# 8Bit-audio-7524-axelb-v2.net
KiCad netlist of a schematic drawn in EAGLE
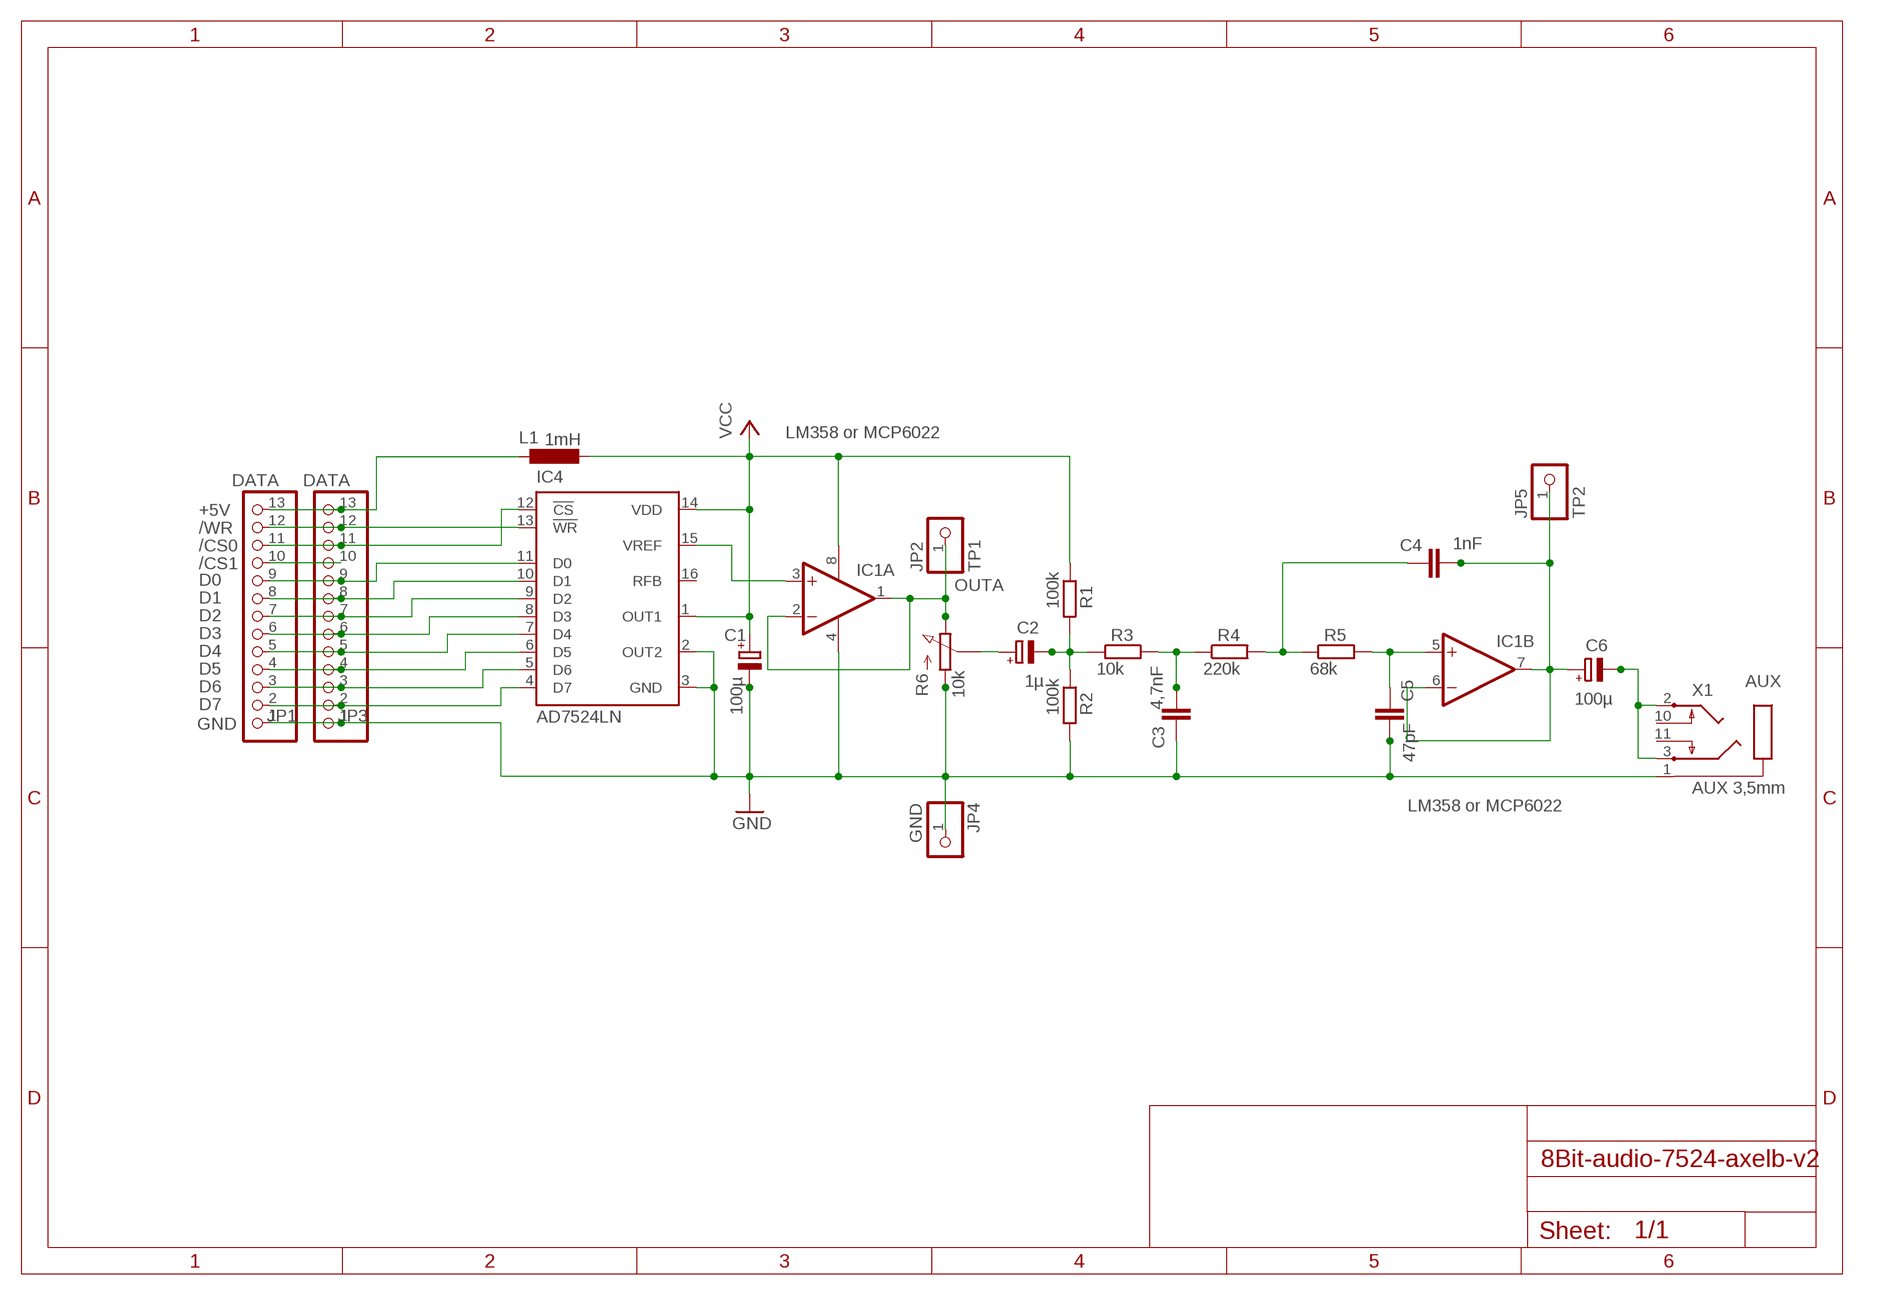
[diagram p0: schematic, sheet 1]

(export (version "E")
  (design (tool "Eeschema 10.0.6"))
  (components
    (comp (ref "C1")
      (value "100µ")
      (footprint "eagle-import:E2,5-7")
      (libsource (lib "eagle-import") (part "CPOL-EUE2.5-7"))
    )
    (comp (ref "C2")
      (value "1µ")
      (footprint "eagle-import:E2,5-7")
      (libsource (lib "eagle-import") (part "CPOL-EUE2.5-7"))
    )
    (comp (ref "C3")
      (value "4,7nF")
      (footprint "eagle-import:RCL_C025_050-055X075")
      (libsource (lib "eagle-import") (part "RCL_C-EU025_050-055X075"))
    )
    (comp (ref "C4")
      (value "1nF")
      (footprint "eagle-import:RCL_C025_050-055X075")
      (libsource (lib "eagle-import") (part "RCL_C-EU025_050-055X075"))
    )
    (comp (ref "C5")
      (value "47pF")
      (footprint "eagle-import:RCL_C025_050-055X075")
      (libsource (lib "eagle-import") (part "RCL_C-EU025_050-055X075"))
    )
    (comp (ref "C6")
      (value "100µ")
      (footprint "eagle-import:E2,5-7")
      (libsource (lib "eagle-import") (part "CPOL-EUE2.5-7"))
    )
    (comp (ref "IC1")
      (value "LM358 or MCP6022")
      (footprint "eagle-import:DIL08")
      (libsource (lib "eagle-import") (part "LM358N"))
    )
    (comp (ref "IC4")
      (value "AD7524LN")
      (footprint "eagle-import:DIL16")
      (fields (field (name "MF") "ALTERA CORPORATION") (field (name "MPN") "AD7524LNZ"))
      (libsource (lib "eagle-import") (part "AD7524NL"))
    )
    (comp (ref "JP1")
      (value "DATA")
      (footprint "eagle-import:1X13")
      (libsource (lib "eagle-import") (part "PINHD-1X13"))
    )
    (comp (ref "JP2")
      (value "TP1")
      (footprint "eagle-import:1X01")
      (libsource (lib "eagle-import") (part "PINHD-1X1"))
    )
    (comp (ref "JP3")
      (value "DATA")
      (footprint "eagle-import:1X13")
      (libsource (lib "eagle-import") (part "PINHD-1X13"))
    )
    (comp (ref "JP4")
      (value "GND")
      (footprint "eagle-import:1X01")
      (libsource (lib "eagle-import") (part "PINHD-1X1"))
    )
    (comp (ref "JP5")
      (value "TP2")
      (footprint "eagle-import:1X01")
      (libsource (lib "eagle-import") (part "PINHD-1X1"))
    )
    (comp (ref "L1")
      (value "1mH")
      (footprint "eagle-import:0207_10")
      (libsource (lib "eagle-import") (part "L-EU0207/10"))
    )
    (comp (ref "R1")
      (value "100k")
      (footprint "eagle-import:0207_10")
      (libsource (lib "eagle-import") (part "R-EU_0207/10"))
    )
    (comp (ref "R2")
      (value "100k")
      (footprint "eagle-import:0207_10")
      (libsource (lib "eagle-import") (part "R-EU_0207/10"))
    )
    (comp (ref "R3")
      (value "10k")
      (footprint "eagle-import:0207_10")
      (libsource (lib "eagle-import") (part "R-EU_0207/10"))
    )
    (comp (ref "R4")
      (value "220k")
      (footprint "eagle-import:0207_10")
      (libsource (lib "eagle-import") (part "R-EU_0207/10"))
    )
    (comp (ref "R5")
      (value "68k")
      (footprint "eagle-import:0207_10")
      (libsource (lib "eagle-import") (part "R-EU_0207/10"))
    )
    (comp (ref "R6")
      (value "10k")
      (footprint "eagle-import:POT_3RP_1610N")
      (libsource (lib "eagle-import") (part "POT_3RP/1610N"))
    )
    (comp (ref "X1")
      (value "AUX 3,5mm")
      (footprint "eagle-import:SJ1-352XN")
      (libsource (lib "eagle-import") (part "CON-SJ1-352XNSJ1-352XN"))
    )
  )
  (nets
    (net (code "1") (name "/+5V") (class "Default")
      (node (ref "JP1") (pin "13") (pinfunction "13_13") (pintype "passive"))
      (node (ref "JP3") (pin "13") (pinfunction "13_13") (pintype "passive"))
      (node (ref "L1") (pin "1") (pinfunction "1_1") (pintype "passive"))
    )
    (net (code "2") (name "/AUX") (class "Default")
      (node (ref "C6") (pin "-") (pinfunction "-_-") (pintype "passive"))
      (node (ref "C6") (pin "-1") (pinfunction "-2_-1") (pintype "passive"))
      (node (ref "X1") (pin "2") (pinfunction "2_2") (pintype "passive"))
      (node (ref "X1") (pin "3") (pinfunction "3_3") (pintype "passive"))
    )
    (net (code "3") (name "/D0") (class "Default")
      (node (ref "IC4") (pin "11") (pinfunction "D0_11") (pintype "input"))
      (node (ref "JP1") (pin "9") (pinfunction "9_9") (pintype "passive"))
      (node (ref "JP3") (pin "9") (pinfunction "9_9") (pintype "passive"))
    )
    (net (code "4") (name "/D1") (class "Default")
      (node (ref "IC4") (pin "10") (pinfunction "D1_10") (pintype "input"))
      (node (ref "JP1") (pin "8") (pinfunction "8_8") (pintype "passive"))
      (node (ref "JP3") (pin "8") (pinfunction "8_8") (pintype "passive"))
    )
    (net (code "5") (name "/D2") (class "Default")
      (node (ref "IC4") (pin "9") (pinfunction "D2_9") (pintype "input"))
      (node (ref "JP1") (pin "7") (pinfunction "7_7") (pintype "passive"))
      (node (ref "JP3") (pin "7") (pinfunction "7_7") (pintype "passive"))
    )
    (net (code "6") (name "/D3") (class "Default")
      (node (ref "IC4") (pin "8") (pinfunction "D3_8") (pintype "input"))
      (node (ref "JP1") (pin "6") (pinfunction "6_6") (pintype "passive"))
      (node (ref "JP3") (pin "6") (pinfunction "6_6") (pintype "passive"))
    )
    (net (code "7") (name "/D4") (class "Default")
      (node (ref "IC4") (pin "7") (pinfunction "D4_7") (pintype "input"))
      (node (ref "JP1") (pin "5") (pinfunction "5_5") (pintype "passive"))
      (node (ref "JP3") (pin "5") (pinfunction "5_5") (pintype "passive"))
    )
    (net (code "8") (name "/D5") (class "Default")
      (node (ref "IC4") (pin "6") (pinfunction "D5_6") (pintype "input"))
      (node (ref "JP1") (pin "4") (pinfunction "4_4") (pintype "passive"))
      (node (ref "JP3") (pin "4") (pinfunction "4_4") (pintype "passive"))
    )
    (net (code "9") (name "/D6") (class "Default")
      (node (ref "IC4") (pin "5") (pinfunction "D6_5") (pintype "input"))
      (node (ref "JP1") (pin "3") (pinfunction "3_3") (pintype "passive"))
      (node (ref "JP3") (pin "3") (pinfunction "3_3") (pintype "passive"))
    )
    (net (code "10") (name "/D7") (class "Default")
      (node (ref "IC4") (pin "4") (pinfunction "D7_4") (pintype "input"))
      (node (ref "JP1") (pin "2") (pinfunction "2_2") (pintype "passive"))
      (node (ref "JP3") (pin "2") (pinfunction "2_2") (pintype "passive"))
    )
    (net (code "11") (name "/OUTA") (class "Default")
      (node (ref "IC1") (pin "1") (pinfunction "OUT_1") (pintype "output"))
      (node (ref "IC1") (pin "2") (pinfunction "-IN_2") (pintype "input"))
      (node (ref "JP2") (pin "1") (pinfunction "1_1") (pintype "passive"))
      (node (ref "R6") (pin "E1") (pinfunction "E1_E1") (pintype "passive"))
      (node (ref "R6") (pin "E2") (pinfunction "E2_E2") (pintype "passive"))
    )
    (net (code "12") (name "/{slash}CS0") (class "Default")
      (node (ref "IC4") (pin "12") (pinfunction "~{CS}_12") (pintype "input"))
      (node (ref "JP1") (pin "11") (pinfunction "11_11") (pintype "passive"))
      (node (ref "JP3") (pin "11") (pinfunction "11_11") (pintype "passive"))
    )
    (net (code "13") (name "/{slash}CS1") (class "Default")
      (node (ref "JP1") (pin "10") (pinfunction "10_10") (pintype "passive"))
      (node (ref "JP3") (pin "10") (pinfunction "10_10") (pintype "passive"))
    )
    (net (code "14") (name "/{slash}WR") (class "Default")
      (node (ref "IC4") (pin "13") (pinfunction "~{WR}_13") (pintype "input"))
      (node (ref "JP1") (pin "12") (pinfunction "12_12") (pintype "passive"))
      (node (ref "JP3") (pin "12") (pinfunction "12_12") (pintype "passive"))
    )
    (net (code "15") (name "GND") (class "Default")
      (node (ref "C1") (pin "-") (pinfunction "-_-") (pintype "passive"))
      (node (ref "C1") (pin "-1") (pinfunction "-2_-1") (pintype "passive"))
      (node (ref "C3") (pin "1") (pinfunction "A1_1") (pintype "passive"))
      (node (ref "C5") (pin "2") (pinfunction "B1_2") (pintype "passive"))
      (node (ref "C5") (pin "3") (pinfunction "B2_3") (pintype "passive"))
      (node (ref "IC1") (pin "4") (pinfunction "V-_4") (pintype "power_in"))
      (node (ref "IC4") (pin "2") (pinfunction "OUT2_2") (pintype "passive"))
      (node (ref "IC4") (pin "3") (pinfunction "GND_3") (pintype "power_in"))
      (node (ref "JP1") (pin "1") (pinfunction "1_1") (pintype "passive"))
      (node (ref "JP3") (pin "1") (pinfunction "1_1") (pintype "passive"))
      (node (ref "JP4") (pin "1") (pinfunction "1_1") (pintype "passive"))
      (node (ref "R2") (pin "2") (pinfunction "2_2") (pintype "passive"))
      (node (ref "R6") (pin "A1") (pinfunction "A1_A1") (pintype "passive"))
      (node (ref "R6") (pin "A2") (pinfunction "A2_A2") (pintype "passive"))
      (node (ref "X1") (pin "1") (pinfunction "1_1") (pintype "passive"))
    )
    (net (code "16") (name "Net-(C2--2)") (class "Default")
      (node (ref "C2") (pin "-") (pinfunction "-_-") (pintype "passive"))
      (node (ref "C2") (pin "-1") (pinfunction "-2_-1") (pintype "passive"))
      (node (ref "R1") (pin "2") (pinfunction "2_2") (pintype "passive"))
      (node (ref "R2") (pin "1") (pinfunction "1_1") (pintype "passive"))
      (node (ref "R3") (pin "1") (pinfunction "1_1") (pintype "passive"))
    )
    (net (code "17") (name "Net-(C3-B1)") (class "Default")
      (node (ref "C3") (pin "2") (pinfunction "B1_2") (pintype "passive"))
      (node (ref "C3") (pin "3") (pinfunction "B2_3") (pintype "passive"))
      (node (ref "R3") (pin "2") (pinfunction "2_2") (pintype "passive"))
      (node (ref "R4") (pin "1") (pinfunction "1_1") (pintype "passive"))
    )
    (net (code "18") (name "Net-(C4-A1)") (class "Default")
      (node (ref "C4") (pin "1") (pinfunction "A1_1") (pintype "passive"))
      (node (ref "R4") (pin "2") (pinfunction "2_2") (pintype "passive"))
      (node (ref "R5") (pin "1") (pinfunction "1_1") (pintype "passive"))
    )
    (net (code "19") (name "Net-(C4-B1)") (class "Default")
      (node (ref "C4") (pin "2") (pinfunction "B1_2") (pintype "passive"))
      (node (ref "C4") (pin "3") (pinfunction "B2_3") (pintype "passive"))
      (node (ref "C6") (pin "+") (pinfunction "+_+") (pintype "passive"))
      (node (ref "IC1") (pin "6") (pinfunction "-IN_6") (pintype "input"))
      (node (ref "IC1") (pin "7") (pinfunction "OUT_7") (pintype "output"))
      (node (ref "JP5") (pin "1") (pinfunction "1_1") (pintype "passive"))
    )
    (net (code "20") (name "Net-(C5-A1)") (class "Default")
      (node (ref "C5") (pin "1") (pinfunction "A1_1") (pintype "passive"))
      (node (ref "IC1") (pin "5") (pinfunction "+IN_5") (pintype "input"))
      (node (ref "R5") (pin "2") (pinfunction "2_2") (pintype "passive"))
    )
    (net (code "21") (name "Net-(IC1A-+IN)") (class "Default")
      (node (ref "IC1") (pin "3") (pinfunction "+IN_3") (pintype "input"))
      (node (ref "IC4") (pin "15") (pinfunction "VREF_15") (pintype "input"))
    )
    (net (code "22") (name "Net-(R6-S)") (class "Default")
      (node (ref "C2") (pin "+") (pinfunction "+_+") (pintype "passive"))
      (node (ref "R6") (pin "M") (pinfunction "S_M") (pintype "passive"))
    )
    (net (code "23") (name "VCC") (class "Default")
      (node (ref "C1") (pin "+") (pinfunction "+_+") (pintype "passive"))
      (node (ref "IC1") (pin "8") (pinfunction "V+_8") (pintype "power_in"))
      (node (ref "IC4") (pin "1") (pinfunction "OUT1_1") (pintype "passive"))
      (node (ref "IC4") (pin "14") (pinfunction "VDD_14") (pintype "power_in"))
      (node (ref "L1") (pin "2") (pinfunction "2_2") (pintype "passive"))
      (node (ref "R1") (pin "1") (pinfunction "1_1") (pintype "passive"))
    )
    (net (code "24") (name "unconnected-(IC4-RFB-Pad16)") (class "Default")
      (node (ref "IC4") (pin "16") (pinfunction "RFB_16") (pintype "passive"))
    )
    (net (code "25") (name "unconnected-(X1-Pad10)") (class "Default")
      (node (ref "X1") (pin "10") (pinfunction "10_10") (pintype "passive"))
    )
    (net (code "26") (name "unconnected-(X1-Pad11)") (class "Default")
      (node (ref "X1") (pin "11") (pinfunction "11_11") (pintype "passive"))
    )
  )
)
